# Arduino_4_Layers_TEST.net
KiCad netlist of a schematic drawn in EAGLE
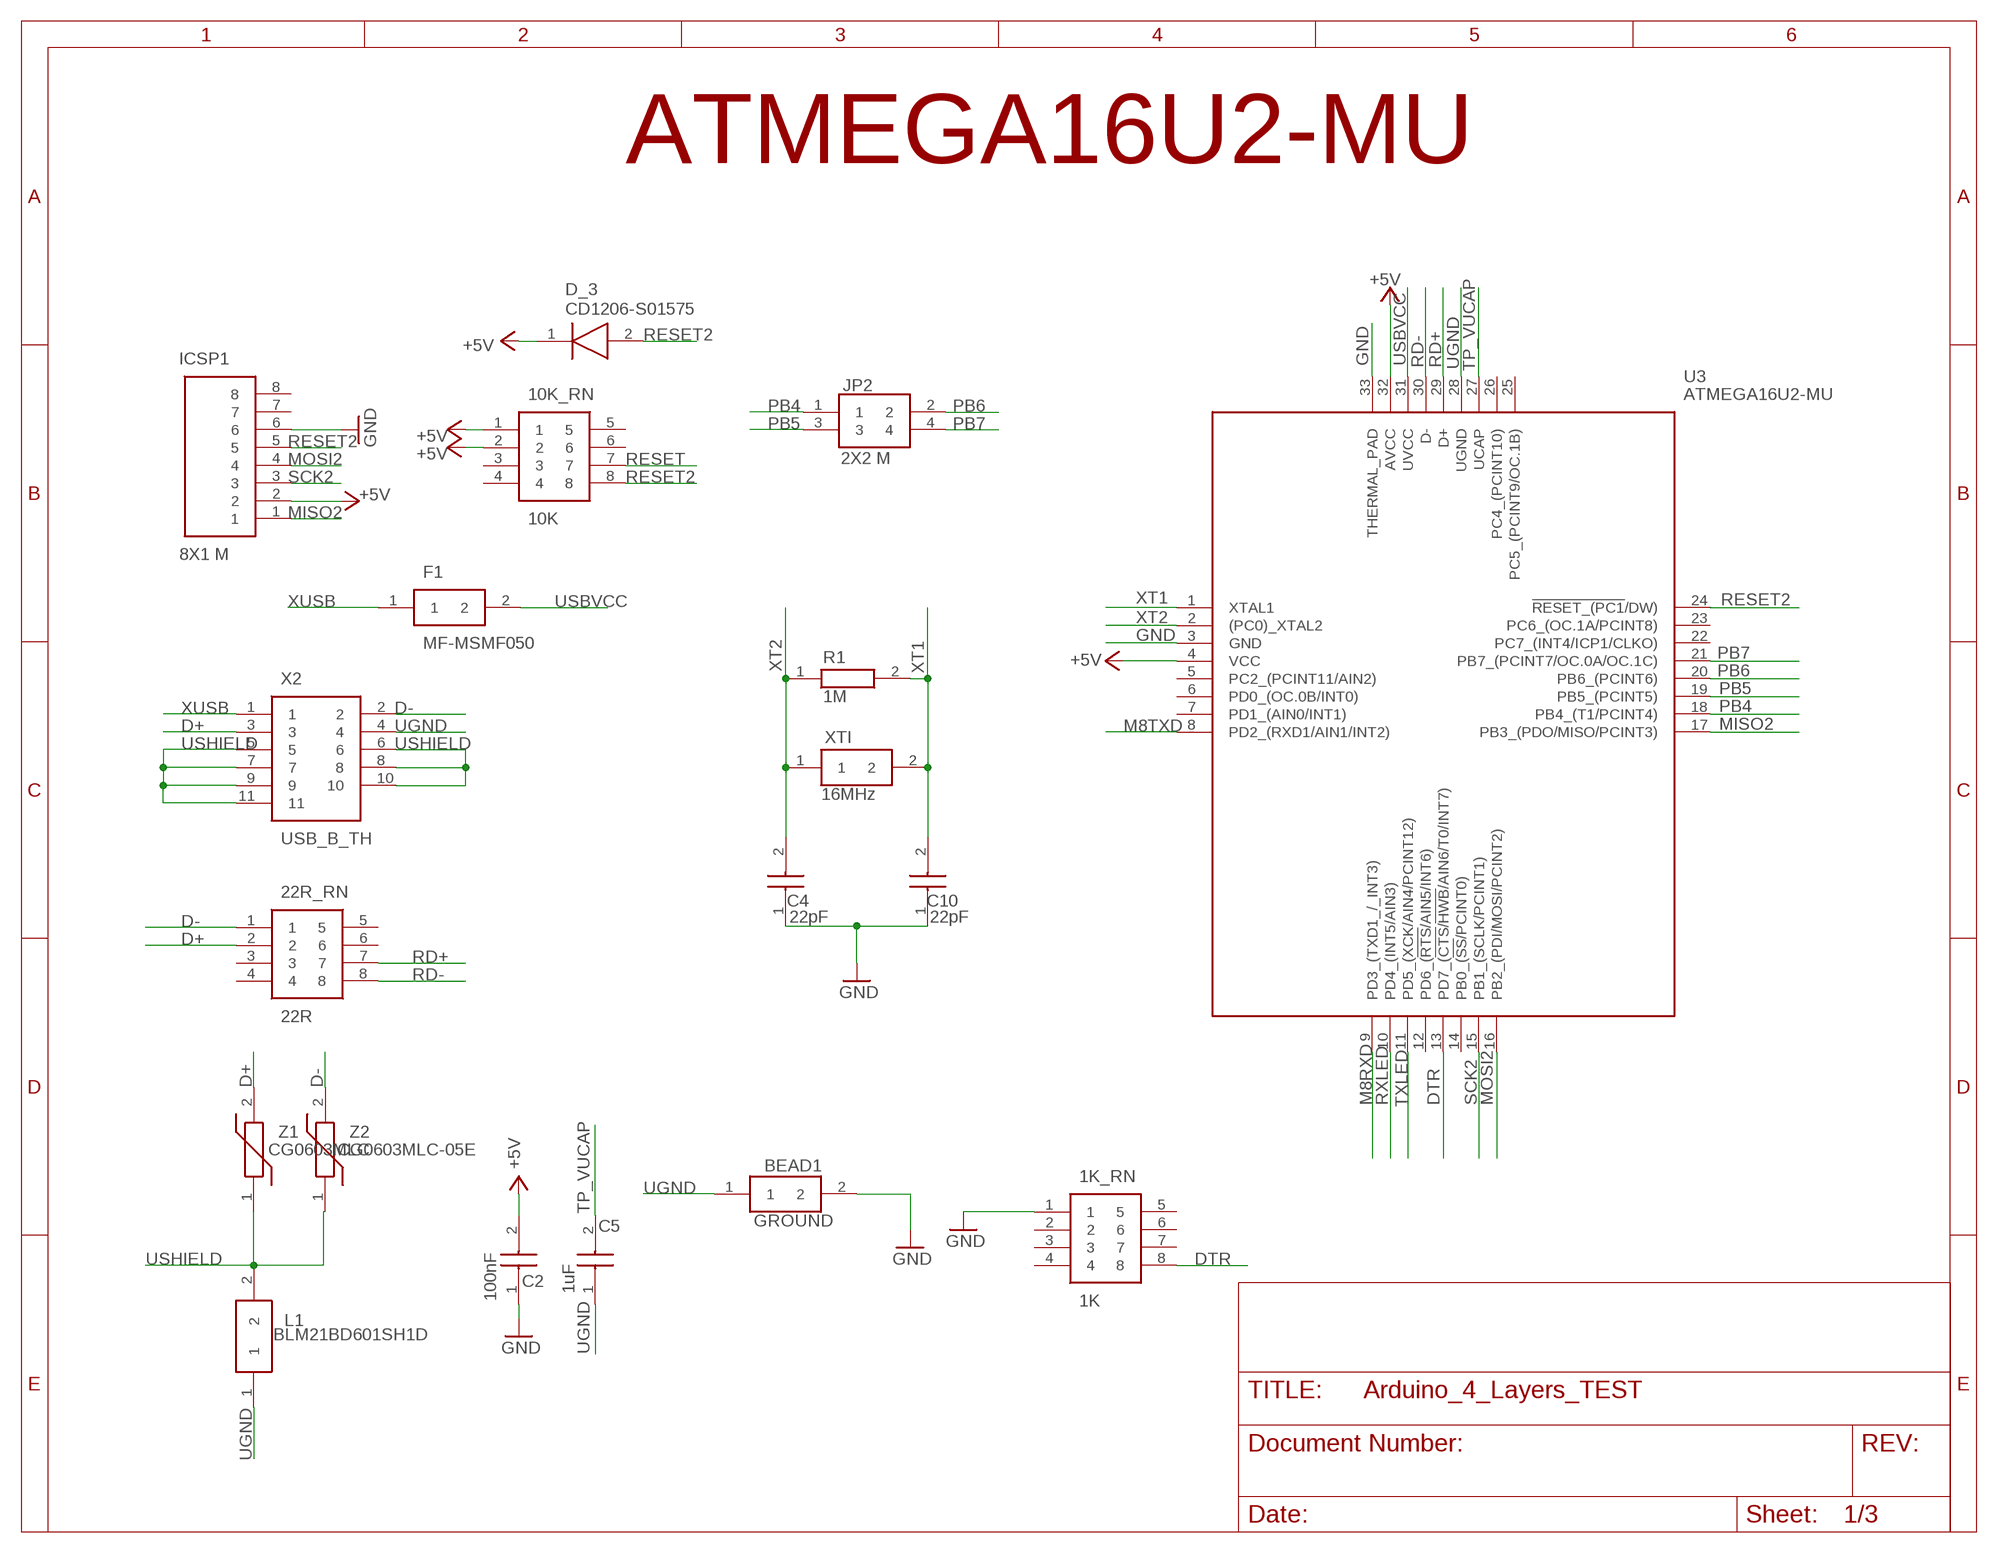
[diagram p0: schematic, sheet 1]
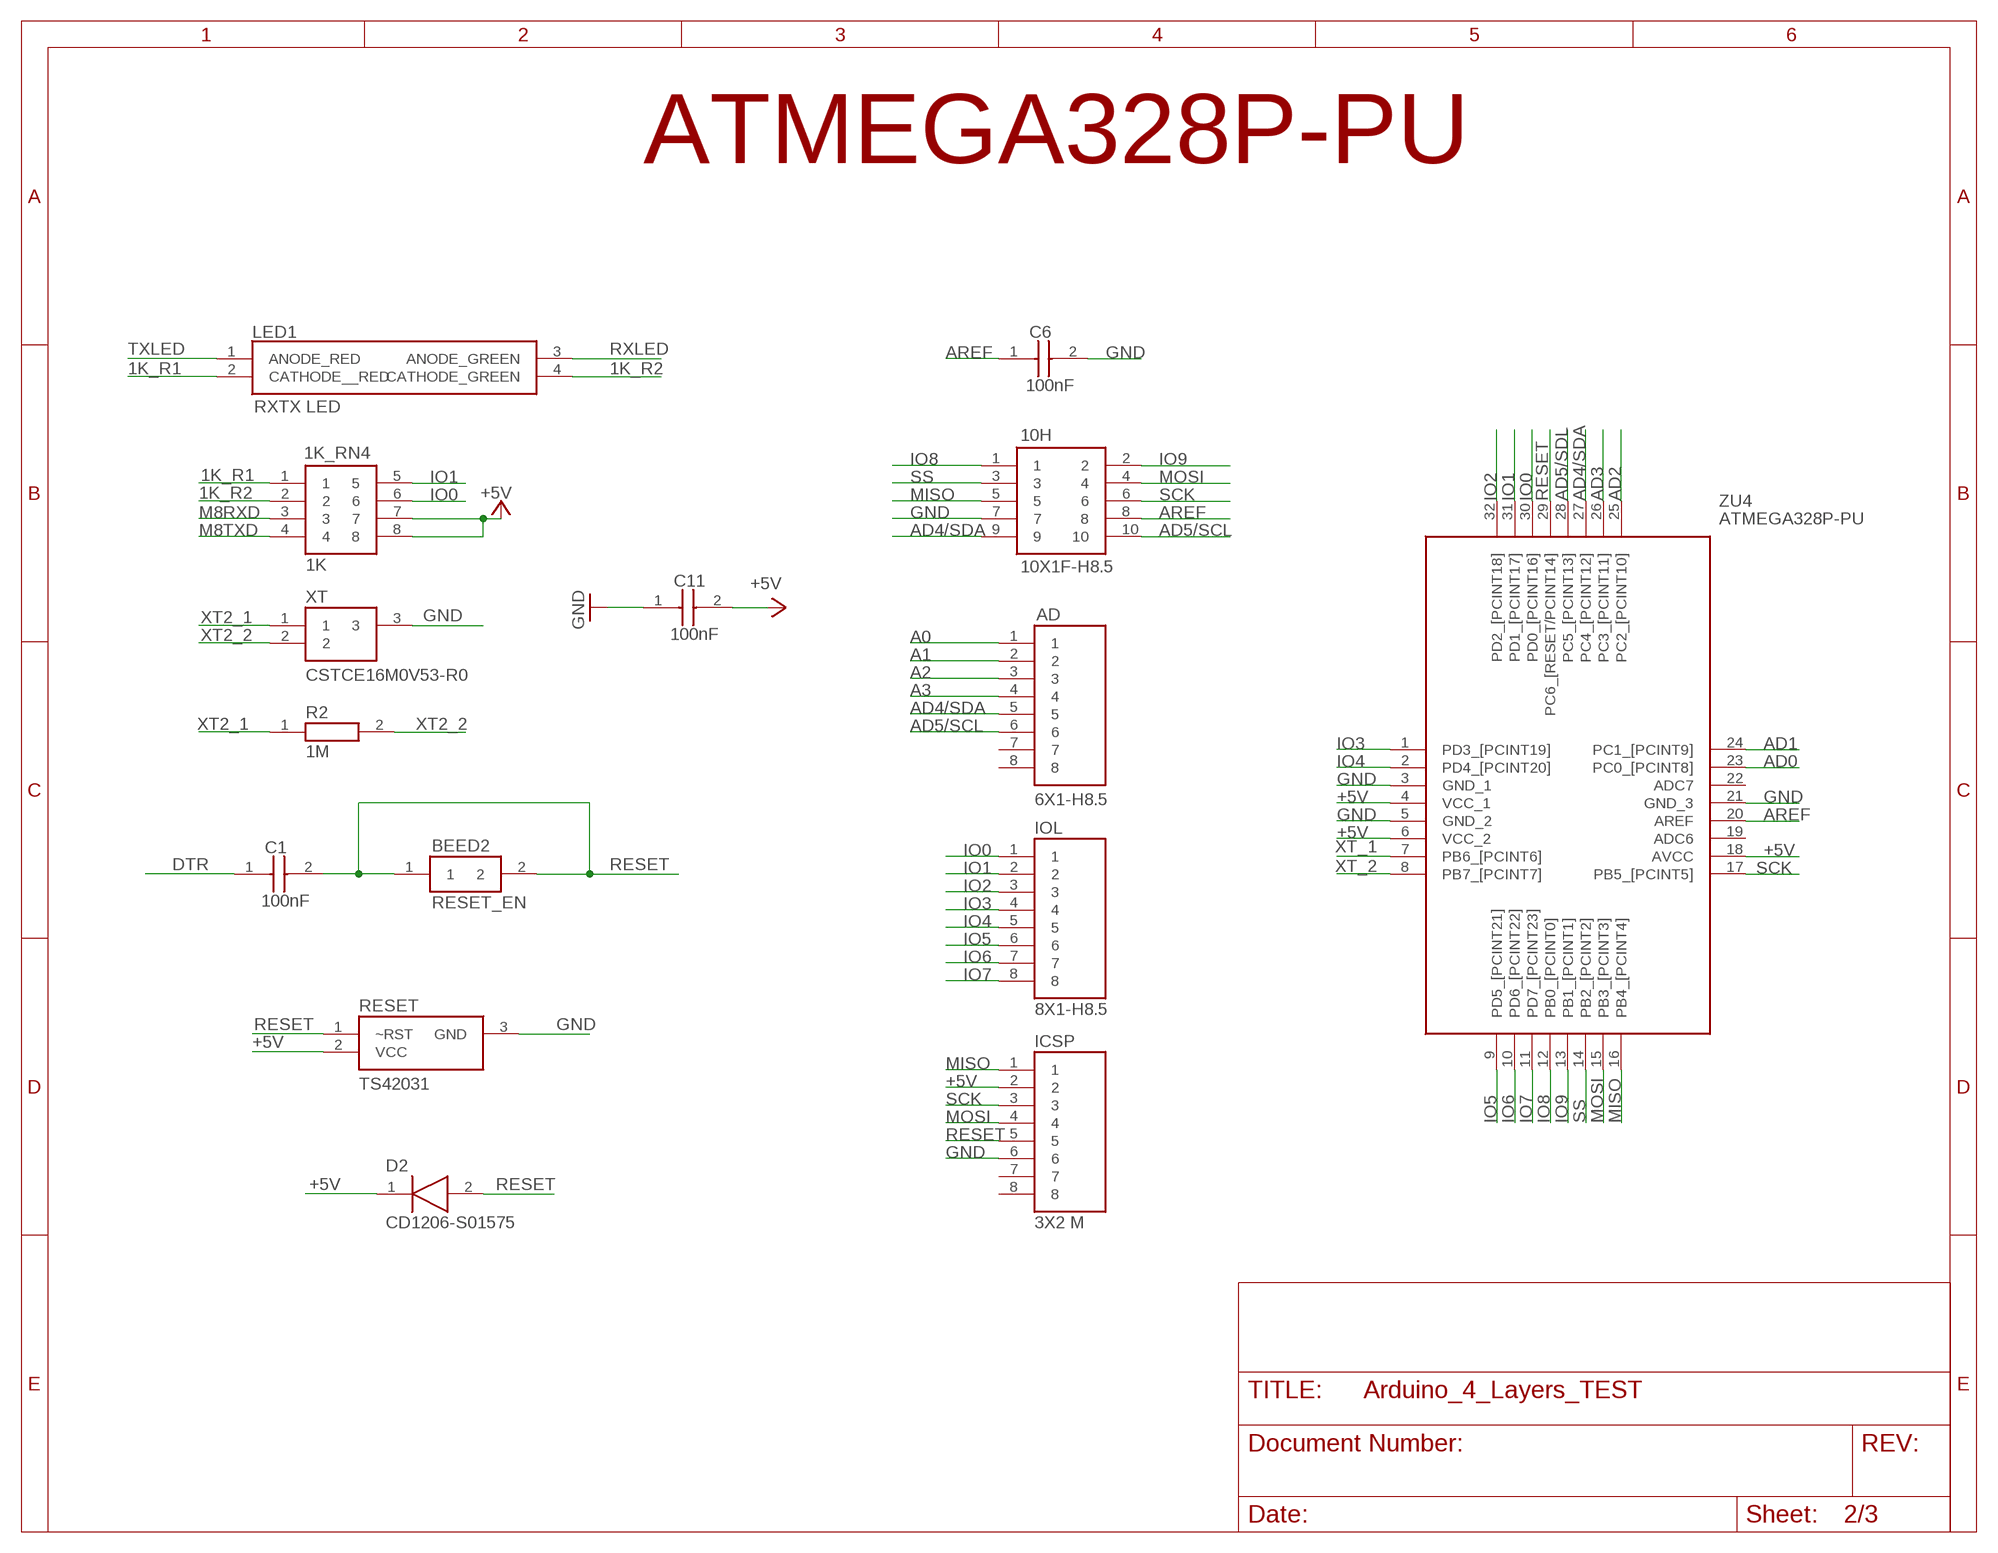
[diagram p1: schematic, sheet 2]
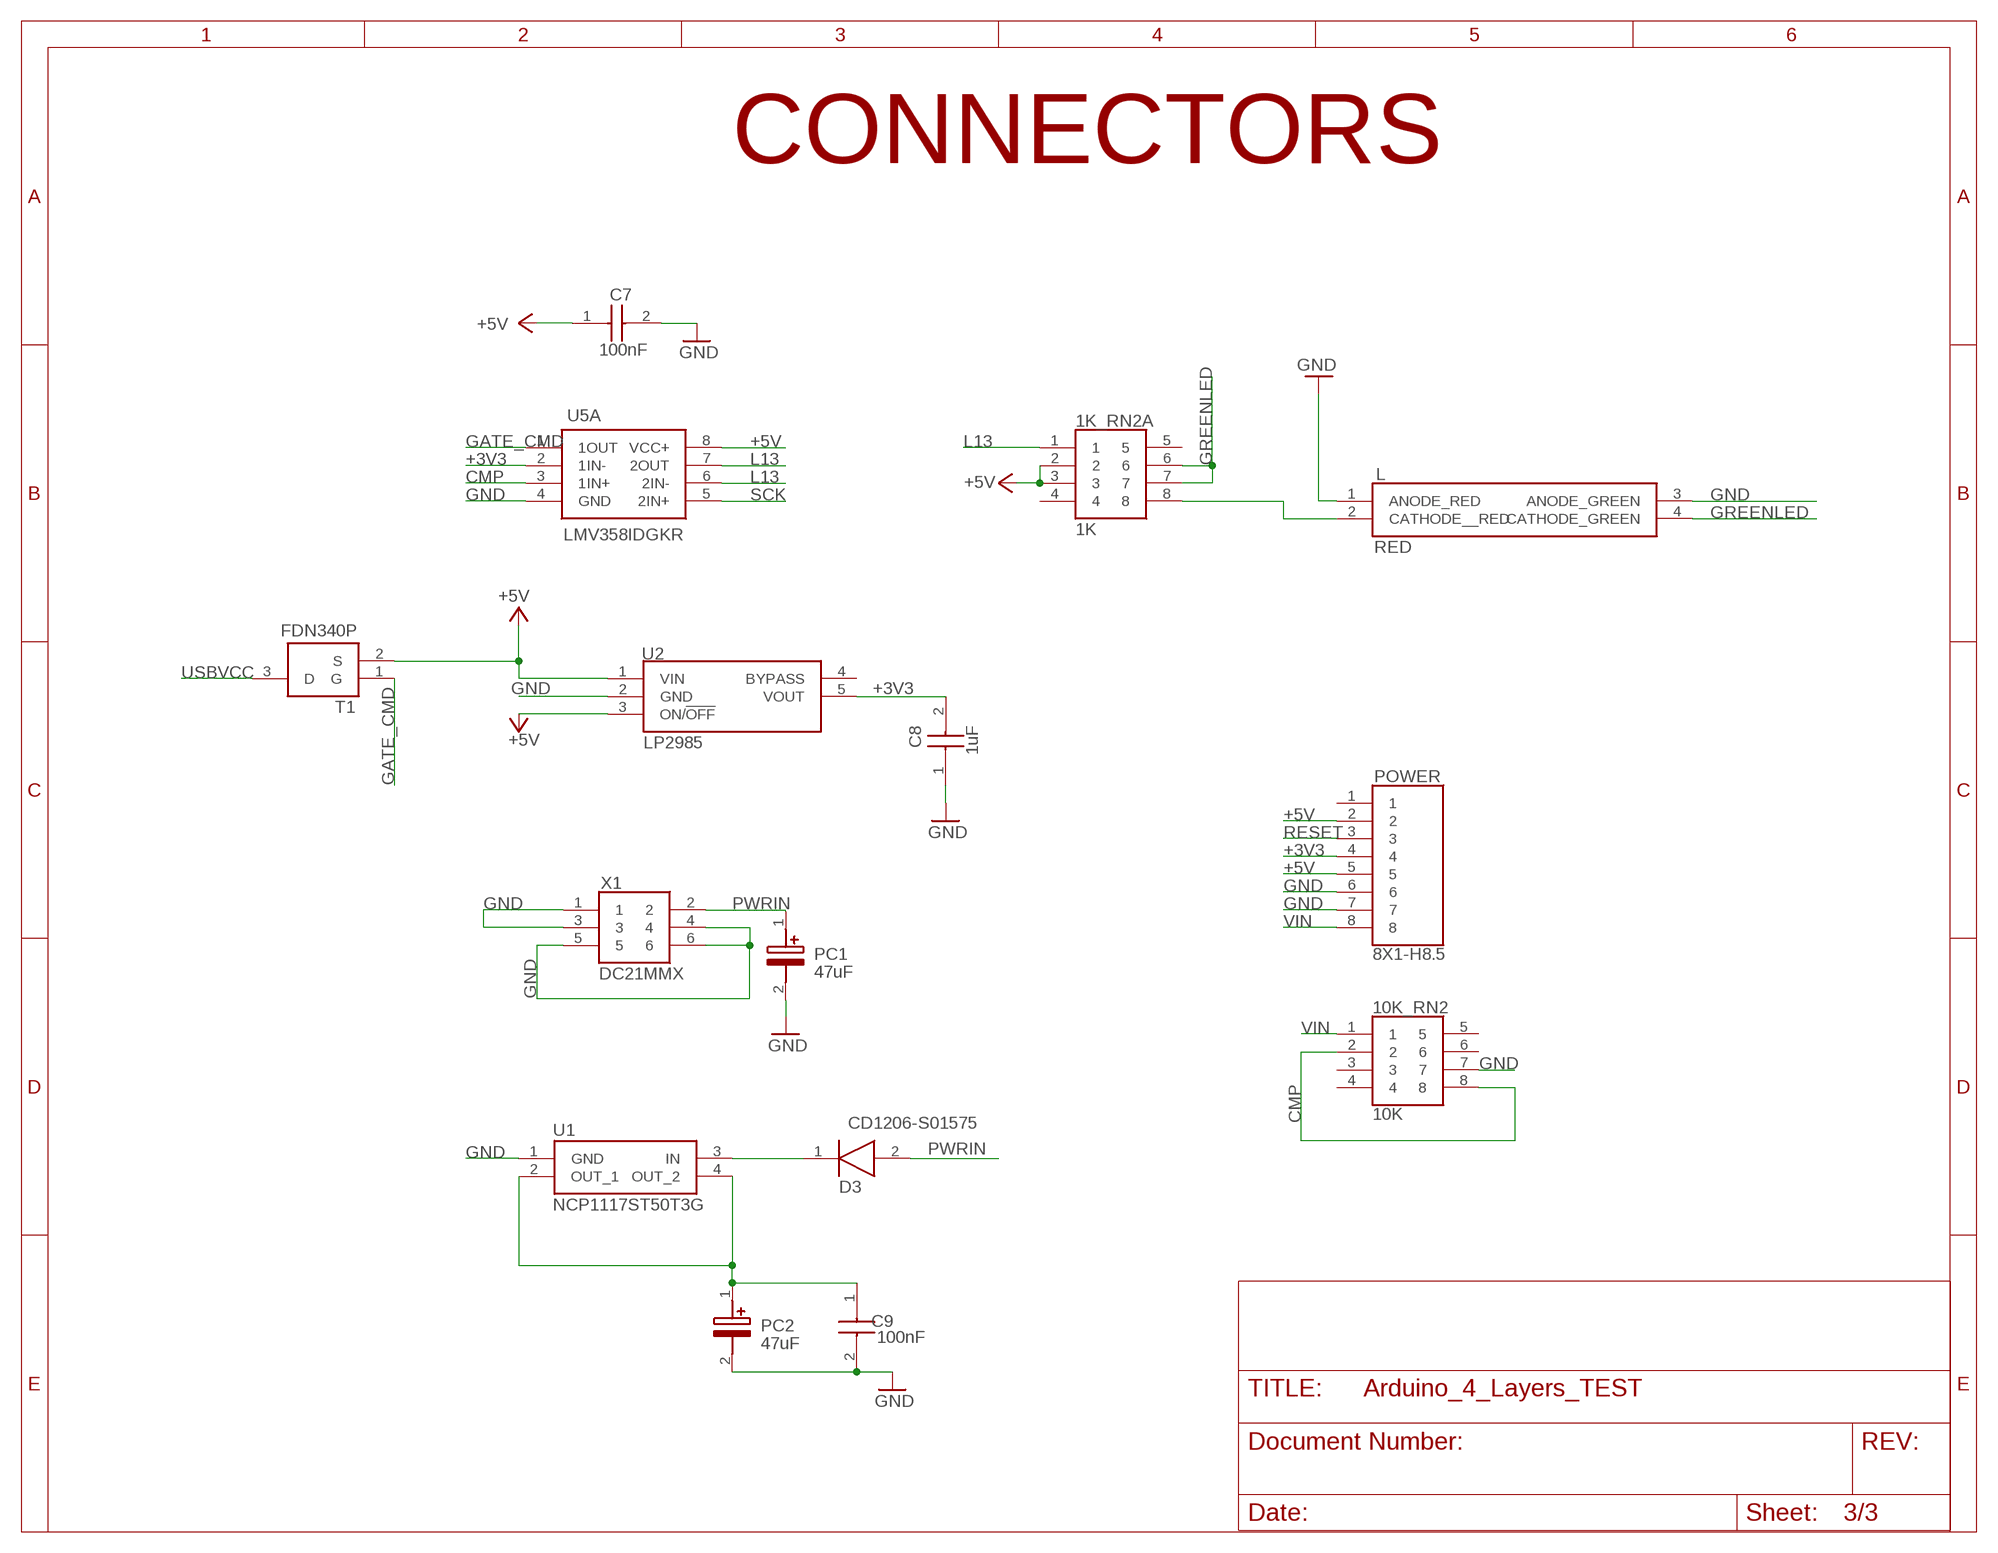
[diagram p2: schematic, sheet 3]

(export (version "E")
  (design (tool "Eeschema 10.0.6"))
  (components
    (comp (ref "1K_RN")
      (value "1K")
      (footprint "eagle-import:CAY10-XXXJ4")
      (fields
        (field (name "MANUFACTURER_PART_NUMBER") "CAY10-220J4LF")
        (field (name "MOUSER_PART_NUMBER") "652-CAY10-220J4LF")
        (field (name "RS_PART_NUMBER") "1674746")
      )
      (libsource (lib "eagle-import") (part "CAY10-220J4LF"))
    )
    (comp (ref "10K_RN")
      (value "10K")
      (footprint "eagle-import:CAY10-XXXJ4")
      (fields
        (field (name "MANUFACTURER_PART_NUMBER") "CAY10-220J4LF")
        (field (name "MOUSER_PART_NUMBER") "652-CAY10-220J4LF")
        (field (name "RS_PART_NUMBER") "1674746")
      )
      (libsource (lib "eagle-import") (part "CAY10-220J4LF"))
    )
    (comp (ref "22R_RN")
      (value "22R")
      (footprint "eagle-import:CAY10-XXXJ4")
      (fields
        (field (name "MANUFACTURER_PART_NUMBER") "CAY10-220J4LF")
        (field (name "MOUSER_PART_NUMBER") "652-CAY10-220J4LF")
        (field (name "RS_PART_NUMBER") "1674746")
      )
      (libsource (lib "eagle-import") (part "CAY10-220J4LF"))
    )
    (comp (ref "BEAD1")
      (value "GROUND")
      (footprint "eagle-import:BEADC2012X105N")
      (fields
        (field (name "MANUFACTURER_PART_NUMBER") "BLM21BD601SH1D")
        (field (name "MOUSER_PART_NUMBER") "81-BLM21BD601SH1D")
        (field (name "RS_PART_NUMBER") "1048541P")
      )
      (libsource (lib "eagle-import") (part "BLM21BD601SH1D"))
    )
    (comp (ref "C2")
      (value "100nF")
      (footprint "eagle-import:CAPC2012X130N")
      (fields
        (field (name "MANUFACTURER_PART_NUMBER") "0805Y0500104KXT")
        (field (name "MOUSER_PART_NUMBER") "7738389P")
      )
      (libsource (lib "eagle-import") (part "0805Y0500104KXT"))
    )
    (comp (ref "C4")
      (value "22pF")
      (footprint "eagle-import:CAPC2012X70N")
      (fields
        (field (name "MANUFACTURER_PART_NUMBER") "GRM2165C1H220JZ01D")
        (field (name "MOUSER_PART_NUMBER") "81-GRM2165C1H220JZ")
        (field (name "RS_PART_NUMBER") "7236243")
      )
      (libsource (lib "eagle-import") (part "GRM2165C1H220JZ01D"))
    )
    (comp (ref "C5")
      (value "1uF")
      (footprint "eagle-import:CAPC2012X145N")
      (fields
        (field (name "MANUFACTURER_PART_NUMBER") "C2012C0G2A103J125AA")
        (field (name "MOUSER_PART_NUMBER") "810-C2012C0G2A103JAA")
      )
      (libsource (lib "eagle-import") (part "C2012C0G2A103J125AA"))
    )
    (comp (ref "C10")
      (value "22pF")
      (footprint "eagle-import:CAPC2012X70N")
      (fields
        (field (name "MANUFACTURER_PART_NUMBER") "GRM2165C1H220JZ01D")
        (field (name "MOUSER_PART_NUMBER") "81-GRM2165C1H220JZ")
        (field (name "RS_PART_NUMBER") "7236243")
      )
      (libsource (lib "eagle-import") (part "GRM2165C1H220JZ01D"))
    )
    (comp (ref "D_3")
      (value "CD1206-S01575")
      (footprint "eagle-import:DIOC3016X65N")
      (fields
        (field (name "MOUSER_PART_NUMBER") "652-CD1206-S01575")
        (field (name "RS_PART_NUMBER") "1775431")
      )
      (libsource (lib "eagle-import") (part "CD1206-S01575"))
    )
    (comp (ref "F1")
      (value "MF-MSMF050")
      (footprint "eagle-import:FUSC4632X75N")
      (fields
        (field (name "MANUFACTURER_PART_NUMBER") "1812L050/30PR")
        (field (name "MOUSER_PART_NUMBER") "576-1812L050/30PR")
        (field (name "RS_PART_NUMBER") "8951631P")
      )
      (libsource (lib "eagle-import") (part "1812L050_30PR"))
    )
    (comp (ref "ICSP1")
      (value "8X1 M")
      (footprint "eagle-import:HDRV8W90P0X254_1X8_2032X249X56")
      (fields
        (field (name "MANUFACTURER_PART_NUMBER") "90120-0768")
        (field (name "MOUSER_PART_NUMBER") "538-90120-0768")
        (field (name "RS_PART_NUMBER") "1671900")
      )
      (libsource (lib "eagle-import") (part "90120-0768"))
    )
    (comp (ref "JP2")
      (value "2X2 M")
      (footprint "eagle-import:HDRV4W77P254_2X2_467X488X821P")
      (fields
        (field (name "MANUFACTURER_PART_NUMBER") "5-146256-2")
        (field (name "MOUSER_PART_NUMBER") "571-5-146256-2")
        (field (name "RS_PART_NUMBER") "7972955")
      )
      (libsource (lib "eagle-import") (part "5-146256-2"))
    )
    (comp (ref "L1")
      (value "BLM21BD601SH1D")
      (footprint "eagle-import:BEADC2012X105N")
      (fields
        (field (name "MOUSER_PART_NUMBER") "81-BLM21BD601SH1D")
        (field (name "RS_PART_NUMBER") "1048541P")
      )
      (libsource (lib "eagle-import") (part "BLM21BD601SH1D"))
    )
    (comp (ref "R1")
      (value "1M")
      (footprint "eagle-import:RESC1608X55N")
      (fields
        (field (name "MANUFACTURER_PART_NUMBER") "CPF0603B1M0E1")
        (field (name "MOUSER_PART_NUMBER") "279-CPF0603B1M0E1")
      )
      (libsource (lib "eagle-import") (part "CPF0603B1M0E1"))
    )
    (comp (ref "U3")
      (value "ATMEGA16U2-MU")
      (footprint "eagle-import:QFN50P500X500X100-33N")
      (fields
        (field (name "MOUSER_PART_NUMBER") "556-ATMEGA16U2-MU")
        (field (name "RS_PART_NUMBER") "1717746")
      )
      (libsource (lib "eagle-import") (part "ATMEGA16U2-MU"))
    )
    (comp (ref "X2")
      (value "USB_B_TH")
      (footprint "eagle-import:17340351")
      (fields
        (field (name "MANUFACTURER_PART_NUMBER") "1734035-1")
        (field (name "MOUSER_PART_NUMBER") "571-1734035-1")
      )
      (libsource (lib "eagle-import") (part "1734035-1"))
    )
    (comp (ref "XTI")
      (value "16MHz")
      (footprint "eagle-import:MODEL-445")
      (fields
        (field (name "MANUFACTURER_PART_NUMBER") "445I35D16M00000")
        (field (name "MOUSER_PART_NUMBER") "774-445I35D16M00000")
      )
      (libsource (lib "eagle-import") (part "445I35D16M00000"))
    )
    (comp (ref "Z1")
      (value "CG0603MLC")
      (footprint "eagle-import:VARC1608X55N")
      (fields
        (field (name "MANUFACTURER_PART_NUMBER") "CG0603MLC-05E")
        (field (name "MOUSER_PART_NUMBER") "652-CG0603MLC-05E")
        (field (name "RS_PART_NUMBER") "8518256")
      )
      (libsource (lib "eagle-import") (part "CG0603MLC-05E"))
    )
    (comp (ref "Z2")
      (value "CG0603MLC-05E")
      (footprint "eagle-import:VARC1608X55N")
      (fields
        (field (name "MOUSER_PART_NUMBER") "652-CG0603MLC-05E")
        (field (name "RS_PART_NUMBER") "8518256")
      )
      (libsource (lib "eagle-import") (part "CG0603MLC-05E"))
    )
    (comp (ref "1K_RN4")
      (value "1K")
      (footprint "eagle-import:CAY10-XXXJ4")
      (fields
        (field (name "MANUFACTURER_PART_NUMBER") "CAY10-220J4LF")
        (field (name "MOUSER_PART_NUMBER") "652-CAY10-220J4LF")
        (field (name "RS_PART_NUMBER") "1674746")
      )
      (libsource (lib "eagle-import") (part "CAY10-220J4LF"))
    )
    (comp (ref "10H")
      (value "10X1F-H8.5")
      (footprint "eagle-import:FTMH10503LDV")
      (fields
        (field (name "MANUFACTURER_PART_NUMBER") "FTMH-105-03-L-DV")
        (field (name "MOUSER_PART_NUMBER") "200-FTMH10503LDV")
        (field (name "RS_PART_NUMBER") "7668984P")
      )
      (libsource (lib "eagle-import") (part "FTMH-105-03-L-DV"))
    )
    (comp (ref "AD")
      (value "6X1-H8.5")
      (footprint "eagle-import:HDRV8W90P0X254_1X8_2032X249X56")
      (fields
        (field (name "MANUFACTURER_PART_NUMBER") "90120-0768")
        (field (name "MOUSER_PART_NUMBER") "538-90120-0768")
        (field (name "RS_PART_NUMBER") "1671900")
      )
      (libsource (lib "eagle-import") (part "90120-0768"))
    )
    (comp (ref "BEED2")
      (value "RESET_EN")
      (footprint "eagle-import:BEADC2012X105N")
      (fields
        (field (name "MANUFACTURER_PART_NUMBER") "BLM21BD601SH1D")
        (field (name "MOUSER_PART_NUMBER") "81-BLM21BD601SH1D")
        (field (name "RS_PART_NUMBER") "1048541P")
      )
      (libsource (lib "eagle-import") (part "BLM21BD601SH1D"))
    )
    (comp (ref "C1")
      (value "100nF")
      (footprint "eagle-import:CAPC2012X130N")
      (fields
        (field (name "MANUFACTURER_PART_NUMBER") "0805Y0500104KXT")
        (field (name "MOUSER_PART_NUMBER") "7738389P")
      )
      (libsource (lib "eagle-import") (part "0805Y0500104KXT"))
    )
    (comp (ref "C6")
      (value "100nF")
      (footprint "eagle-import:CAPC2012X130N")
      (fields
        (field (name "MANUFACTURER_PART_NUMBER") "0805Y0500104KXT")
        (field (name "MOUSER_PART_NUMBER") "7738389P")
      )
      (libsource (lib "eagle-import") (part "0805Y0500104KXT"))
    )
    (comp (ref "C11")
      (value "100nF")
      (footprint "eagle-import:CAPC2012X130N")
      (fields
        (field (name "MANUFACTURER_PART_NUMBER") "0805Y0500104KXT")
        (field (name "MOUSER_PART_NUMBER") "7738389P")
      )
      (libsource (lib "eagle-import") (part "0805Y0500104KXT"))
    )
    (comp (ref "D2")
      (value "CD1206-S01575")
      (footprint "eagle-import:DIOC3016X65N")
      (fields
        (field (name "MOUSER_PART_NUMBER") "652-CD1206-S01575")
        (field (name "RS_PART_NUMBER") "1775431")
      )
      (libsource (lib "eagle-import") (part "CD1206-S01575"))
    )
    (comp (ref "ICSP")
      (value "3X2 M")
      (footprint "eagle-import:HDRV8W90P0X254_1X8_2032X249X56")
      (fields
        (field (name "MANUFACTURER_PART_NUMBER") "90120-0768")
        (field (name "MOUSER_PART_NUMBER") "538-90120-0768")
        (field (name "RS_PART_NUMBER") "1671900")
      )
      (libsource (lib "eagle-import") (part "90120-0768"))
    )
    (comp (ref "IOL")
      (value "8X1-H8.5")
      (footprint "eagle-import:HDRV8W90P0X254_1X8_2032X249X56")
      (fields
        (field (name "MANUFACTURER_PART_NUMBER") "90120-0768")
        (field (name "MOUSER_PART_NUMBER") "538-90120-0768")
        (field (name "RS_PART_NUMBER") "1671900")
      )
      (libsource (lib "eagle-import") (part "90120-0768"))
    )
    (comp (ref "LED1")
      (value "RXTX LED")
      (footprint "eagle-import:SML522MD8WT86")
      (fields
        (field (name "MANUFACTURER_PART_NUMBER") "SML-522MU8WT86")
        (field (name "MOUSER_PART_NUMBER") "755-SML-522MU8WT86")
        (field (name "RS_PART_NUMBER") "1682468")
      )
      (libsource (lib "eagle-import") (part "SML-522MU8WT86"))
    )
    (comp (ref "R2")
      (value "1M")
      (footprint "eagle-import:RESC1608X55N")
      (fields
        (field (name "MANUFACTURER_PART_NUMBER") "CPF0603B1M0E1")
        (field (name "MOUSER_PART_NUMBER") "279-CPF0603B1M0E1")
      )
      (libsource (lib "eagle-import") (part "CPF0603B1M0E1"))
    )
    (comp (ref "RESET")
      (value "TS42031")
      (footprint "eagle-import:SOT95P240X110-3N")
      (fields (field (name "MANUFACTURER_PART_NUMBER") "DS1818R-5+"))
      (libsource (lib "eagle-import") (part "DS1818R-5+"))
    )
    (comp (ref "XT")
      (value "CSTCE16M0V53-R0")
      (footprint "eagle-import:CSTCE-V")
      (fields
        (field (name "MOUSER_PART_NUMBER") "81-CSTCE16M0V53-R0")
        (field (name "RS_PART_NUMBER") "7926524P")
      )
      (libsource (lib "eagle-import") (part "CSTCE16M0V53-R0"))
    )
    (comp (ref "ZU4")
      (value "ATMEGA328P-PU")
      (footprint "eagle-import:QFP80P900X900X120-32N")
      (fields
        (field (name "MANUFACTURER_PART_NUMBER") "ATMEGA328P-AU")
        (field (name "MOUSER_PART_NUMBER") "556-ATMEGA328P-AU")
        (field (name "RS_PART_NUMBER") "1310271")
      )
      (libsource (lib "eagle-import") (part "ATMEGA328P-AU"))
    )
    (comp (ref "1K_RN2A")
      (value "1K")
      (footprint "eagle-import:CAY10-XXXJ4")
      (fields
        (field (name "MANUFACTURER_PART_NUMBER") "CAY10-220J4LF")
        (field (name "MOUSER_PART_NUMBER") "652-CAY10-220J4LF")
        (field (name "RS_PART_NUMBER") "1674746")
      )
      (libsource (lib "eagle-import") (part "CAY10-220J4LF"))
    )
    (comp (ref "10K_RN2")
      (value "10K")
      (footprint "eagle-import:CAY10-XXXJ4")
      (fields
        (field (name "MANUFACTURER_PART_NUMBER") "CAY10-220J4LF")
        (field (name "MOUSER_PART_NUMBER") "652-CAY10-220J4LF")
        (field (name "RS_PART_NUMBER") "1674746")
      )
      (libsource (lib "eagle-import") (part "CAY10-220J4LF"))
    )
    (comp (ref "C7")
      (value "100nF")
      (footprint "eagle-import:CAPC2012X130N")
      (fields
        (field (name "MANUFACTURER_PART_NUMBER") "0805Y0500104KXT")
        (field (name "MOUSER_PART_NUMBER") "7738389P")
      )
      (libsource (lib "eagle-import") (part "0805Y0500104KXT"))
    )
    (comp (ref "C8")
      (value "1uF")
      (footprint "eagle-import:CAPC2012X145N")
      (fields
        (field (name "MANUFACTURER_PART_NUMBER") "C2012C0G2A103J125AA")
        (field (name "MOUSER_PART_NUMBER") "810-C2012C0G2A103JAA")
      )
      (libsource (lib "eagle-import") (part "C2012C0G2A103J125AA"))
    )
    (comp (ref "C9")
      (value "100nF")
      (footprint "eagle-import:CAPC2012X130N")
      (fields
        (field (name "MANUFACTURER_PART_NUMBER") "0805Y0500104KXT")
        (field (name "MOUSER_PART_NUMBER") "7738389P")
      )
      (libsource (lib "eagle-import") (part "0805Y0500104KXT"))
    )
    (comp (ref "D3")
      (value "CD1206-S01575")
      (footprint "eagle-import:DIOC3016X65N")
      (fields
        (field (name "MOUSER_PART_NUMBER") "652-CD1206-S01575")
        (field (name "RS_PART_NUMBER") "1775431")
      )
      (libsource (lib "eagle-import") (part "CD1206-S01575"))
    )
    (comp (ref "L")
      (value "RED")
      (footprint "eagle-import:SML522MD8WT86")
      (fields
        (field (name "MANUFACTURER_PART_NUMBER") "SML-522MU8WT86")
        (field (name "MOUSER_PART_NUMBER") "755-SML-522MU8WT86")
        (field (name "RS_PART_NUMBER") "1682468")
      )
      (libsource (lib "eagle-import") (part "SML-522MU8WT86"))
    )
    (comp (ref "PC1")
      (value "47uF")
      (footprint "eagle-import:CAPAE530X610N")
      (fields
        (field (name "MANUFACTURER_PART_NUMBER") "EEE-FT1V470AR")
        (field (name "MOUSER_PART_NUMBER") "667-EEE-FT1V470AR")
      )
      (libsource (lib "eagle-import") (part "EEE-FT1V470AR"))
    )
    (comp (ref "PC2")
      (value "47uF")
      (footprint "eagle-import:CAPAE530X610N")
      (fields
        (field (name "MANUFACTURER_PART_NUMBER") "EEE-FT1V470AR")
        (field (name "MOUSER_PART_NUMBER") "667-EEE-FT1V470AR")
      )
      (libsource (lib "eagle-import") (part "EEE-FT1V470AR"))
    )
    (comp (ref "POWER")
      (value "8X1-H8.5")
      (footprint "eagle-import:HDRV8W90P0X254_1X8_2032X249X56")
      (fields
        (field (name "MANUFACTURER_PART_NUMBER") "90120-0768")
        (field (name "MOUSER_PART_NUMBER") "538-90120-0768")
        (field (name "RS_PART_NUMBER") "1671900")
      )
      (libsource (lib "eagle-import") (part "90120-0768"))
    )
    (comp (ref "T1")
      (value "FDN340P")
      (footprint "eagle-import:SOT95P251X112-3N")
      (fields (field (name "MOUSER_PART_NUMBER") "512-FDN340P") (field (name "RS_PART_NUMBER") "6710435P"))
      (libsource (lib "eagle-import") (part "FDN340P"))
    )
    (comp (ref "U1")
      (value "NCP1117ST50T3G")
      (footprint "eagle-import:SOT230P700X180-4N")
      (fields
        (field (name "MOUSER_PART_NUMBER") "863-NCP1117ST50T3G")
        (field (name "RS_PART_NUMBER") "8022130P")
      )
      (libsource (lib "eagle-import") (part "NCP1117ST50T3G"))
    )
    (comp (ref "U2")
      (value "LP2985")
      (footprint "eagle-import:SOT95P280X145-5N")
      (fields
        (field (name "MANUFACTURER_PART_NUMBER") "LP2985-33DBVR")
        (field (name "MOUSER_PART_NUMBER") "595-LP2985-33DBVR")
      )
      (libsource (lib "eagle-import") (part "LP2985-33DBVR"))
    )
    (comp (ref "U5A")
      (value "LMV358IDGKR")
      (footprint "eagle-import:SOP65P490X110-8N")
      (fields (field (name "MOUSER_PART_NUMBER") "595-LMV358IDGKR") (field (name "RS_PART_NUMBER") "1625114"))
      (libsource (lib "eagle-import") (part "LMV358IDGKR"))
    )
    (comp (ref "X1")
      (value "DC21MMX")
      (footprint "eagle-import:USBBSRA")
      (fields (field (name "MANUFACTURER_PART_NUMBER") "USB-B-S-RA"))
      (libsource (lib "eagle-import") (part "USB-B-S-RA"))
    )
  )
  (nets
    (net (code "1") (name "+3V3") (class "Default")
      (node (ref "C8") (pin "2") (pinfunction "2_2") (pintype "bidirectional"))
      (node (ref "POWER") (pin "4") (pinfunction "4_4") (pintype "bidirectional"))
      (node (ref "U2") (pin "5") (pinfunction "VOUT_5") (pintype "output"))
      (node (ref "U5A") (pin "2") (pinfunction "1IN-_2") (pintype "input"))
    )
    (net (code "2") (name "+5V") (class "Default")
      (node (ref "10K_RN") (pin "1") (pinfunction "1_1") (pintype "bidirectional"))
      (node (ref "10K_RN") (pin "2") (pinfunction "2_2") (pintype "bidirectional"))
      (node (ref "1K_RN2A") (pin "2") (pinfunction "2_2") (pintype "bidirectional"))
      (node (ref "1K_RN2A") (pin "3") (pinfunction "3_3") (pintype "bidirectional"))
      (node (ref "1K_RN4") (pin "7") (pinfunction "7_7") (pintype "bidirectional"))
      (node (ref "1K_RN4") (pin "8") (pinfunction "8_8") (pintype "bidirectional"))
      (node (ref "C11") (pin "2") (pinfunction "2_2") (pintype "bidirectional"))
      (node (ref "C2") (pin "2") (pinfunction "2_2") (pintype "bidirectional"))
      (node (ref "C7") (pin "1") (pinfunction "1_1") (pintype "bidirectional"))
      (node (ref "D2") (pin "1") (pinfunction "K_1") (pintype "bidirectional"))
      (node (ref "D_3") (pin "1") (pinfunction "K_1") (pintype "bidirectional"))
      (node (ref "ICSP") (pin "2") (pinfunction "2_2") (pintype "bidirectional"))
      (node (ref "ICSP1") (pin "2") (pinfunction "2_2") (pintype "bidirectional"))
      (node (ref "POWER") (pin "2") (pinfunction "2_2") (pintype "bidirectional"))
      (node (ref "POWER") (pin "5") (pinfunction "5_5") (pintype "bidirectional"))
      (node (ref "RESET") (pin "2") (pinfunction "VCC_2") (pintype "bidirectional"))
      (node (ref "T1") (pin "2") (pinfunction "S_2") (pintype "bidirectional"))
      (node (ref "U2") (pin "1") (pinfunction "VIN_1") (pintype "power_in"))
      (node (ref "U2") (pin "3") (pinfunction "ON/~{OFF}_3") (pintype "input"))
      (node (ref "U3") (pin "32") (pinfunction "AVCC_32") (pintype "bidirectional"))
      (node (ref "U3") (pin "4") (pinfunction "VCC_4") (pintype "bidirectional"))
      (node (ref "U5A") (pin "8") (pinfunction "VCC+_8") (pintype "power_in"))
      (node (ref "ZU4") (pin "18") (pinfunction "AVCC_18") (pintype "power_in"))
      (node (ref "ZU4") (pin "4") (pinfunction "VCC_1_4") (pintype "power_in"))
      (node (ref "ZU4") (pin "6") (pinfunction "VCC_2_6") (pintype "power_in"))
    )
    (net (code "3") (name "1K_R1") (class "Default")
      (node (ref "1K_RN4") (pin "1") (pinfunction "1_1") (pintype "bidirectional"))
      (node (ref "LED1") (pin "2") (pinfunction "CATHODE__RED_2") (pintype "bidirectional"))
    )
    (net (code "4") (name "1K_R2") (class "Default")
      (node (ref "1K_RN4") (pin "2") (pinfunction "2_2") (pintype "bidirectional"))
      (node (ref "LED1") (pin "4") (pinfunction "CATHODE_GREEN_4") (pintype "bidirectional"))
    )
    (net (code "5") (name "A0") (class "Default")
      (node (ref "AD") (pin "1") (pinfunction "1_1") (pintype "bidirectional"))
    )
    (net (code "6") (name "A1") (class "Default")
      (node (ref "AD") (pin "2") (pinfunction "2_2") (pintype "bidirectional"))
    )
    (net (code "7") (name "A2") (class "Default")
      (node (ref "AD") (pin "3") (pinfunction "3_3") (pintype "bidirectional"))
    )
    (net (code "8") (name "A3") (class "Default")
      (node (ref "AD") (pin "4") (pinfunction "4_4") (pintype "bidirectional"))
    )
    (net (code "9") (name "AD0") (class "Default")
      (node (ref "ZU4") (pin "23") (pinfunction "PC0_[PCINT8]_23") (pintype "bidirectional"))
    )
    (net (code "10") (name "AD1") (class "Default")
      (node (ref "ZU4") (pin "24") (pinfunction "PC1_[PCINT9]_24") (pintype "bidirectional"))
    )
    (net (code "11") (name "AD2") (class "Default")
      (node (ref "ZU4") (pin "25") (pinfunction "PC2_[PCINT10]_25") (pintype "bidirectional"))
    )
    (net (code "12") (name "AD3") (class "Default")
      (node (ref "ZU4") (pin "26") (pinfunction "PC3_[PCINT11]_26") (pintype "bidirectional"))
    )
    (net (code "13") (name "AD4{slash}SDA") (class "Default")
      (node (ref "10H") (pin "9") (pinfunction "9_9") (pintype "bidirectional"))
      (node (ref "AD") (pin "5") (pinfunction "5_5") (pintype "bidirectional"))
      (node (ref "ZU4") (pin "27") (pinfunction "PC4_[PCINT12]_27") (pintype "bidirectional"))
    )
    (net (code "14") (name "AD5{slash}SCL") (class "Default")
      (node (ref "10H") (pin "10") (pinfunction "10_10") (pintype "bidirectional"))
      (node (ref "AD") (pin "6") (pinfunction "6_6") (pintype "bidirectional"))
    )
    (net (code "15") (name "AD5{slash}SDL") (class "Default")
      (node (ref "ZU4") (pin "28") (pinfunction "PC5_[PCINT13]_28") (pintype "bidirectional"))
    )
    (net (code "16") (name "AREF") (class "Default")
      (node (ref "10H") (pin "8") (pinfunction "8_8") (pintype "bidirectional"))
      (node (ref "C6") (pin "1") (pinfunction "1_1") (pintype "bidirectional"))
      (node (ref "ZU4") (pin "20") (pinfunction "AREF_20") (pintype "bidirectional"))
    )
    (net (code "17") (name "CMP") (class "Default")
      (node (ref "10K_RN2") (pin "2") (pinfunction "2_2") (pintype "bidirectional"))
      (node (ref "10K_RN2") (pin "8") (pinfunction "8_8") (pintype "bidirectional"))
      (node (ref "U5A") (pin "3") (pinfunction "1IN+_3") (pintype "input"))
    )
    (net (code "18") (name "D+") (class "Default")
      (node (ref "22R_RN") (pin "2") (pinfunction "2_2") (pintype "bidirectional"))
      (node (ref "X2") (pin "3") (pinfunction "3_3") (pintype "bidirectional"))
      (node (ref "Z1") (pin "2") (pinfunction "2_2") (pintype "bidirectional"))
    )
    (net (code "19") (name "D-") (class "Default")
      (node (ref "22R_RN") (pin "1") (pinfunction "1_1") (pintype "bidirectional"))
      (node (ref "X2") (pin "2") (pinfunction "2_2") (pintype "bidirectional"))
      (node (ref "Z2") (pin "2") (pinfunction "2_2") (pintype "bidirectional"))
    )
    (net (code "20") (name "DTR") (class "Default")
      (node (ref "1K_RN") (pin "8") (pinfunction "8_8") (pintype "bidirectional"))
      (node (ref "C1") (pin "1") (pinfunction "1_1") (pintype "bidirectional"))
      (node (ref "U3") (pin "13") (pinfunction "PD7_(~{CTS}/~{HWB}/AIN6/T0/INT7)_13") (pintype "bidirectional"))
    )
    (net (code "21") (name "GATE_CMD") (class "Default")
      (node (ref "T1") (pin "1") (pinfunction "G_1") (pintype "bidirectional"))
      (node (ref "U5A") (pin "1") (pinfunction "1OUT_1") (pintype "output"))
    )
    (net (code "22") (name "GND") (class "Default")
      (node (ref "10H") (pin "7") (pinfunction "7_7") (pintype "bidirectional"))
      (node (ref "10K_RN2") (pin "7") (pinfunction "7_7") (pintype "bidirectional"))
      (node (ref "1K_RN") (pin "1") (pinfunction "1_1") (pintype "bidirectional"))
      (node (ref "BEAD1") (pin "2") (pinfunction "2_2") (pintype "bidirectional"))
      (node (ref "C10") (pin "1") (pinfunction "1_1") (pintype "bidirectional"))
      (node (ref "C11") (pin "1") (pinfunction "1_1") (pintype "bidirectional"))
      (node (ref "C2") (pin "1") (pinfunction "1_1") (pintype "bidirectional"))
      (node (ref "C4") (pin "1") (pinfunction "1_1") (pintype "bidirectional"))
      (node (ref "C6") (pin "2") (pinfunction "2_2") (pintype "bidirectional"))
      (node (ref "C7") (pin "2") (pinfunction "2_2") (pintype "bidirectional"))
      (node (ref "C8") (pin "1") (pinfunction "1_1") (pintype "bidirectional"))
      (node (ref "C9") (pin "2") (pinfunction "2_2") (pintype "bidirectional"))
      (node (ref "ICSP") (pin "6") (pinfunction "6_6") (pintype "bidirectional"))
      (node (ref "ICSP1") (pin "6") (pinfunction "6_6") (pintype "bidirectional"))
      (node (ref "L") (pin "1") (pinfunction "ANODE_RED_1") (pintype "bidirectional"))
      (node (ref "L") (pin "3") (pinfunction "ANODE_GREEN_3") (pintype "bidirectional"))
      (node (ref "PC1") (pin "2") (pinfunction "-_2") (pintype "bidirectional"))
      (node (ref "PC2") (pin "2") (pinfunction "-_2") (pintype "bidirectional"))
      (node (ref "POWER") (pin "6") (pinfunction "6_6") (pintype "bidirectional"))
      (node (ref "POWER") (pin "7") (pinfunction "7_7") (pintype "bidirectional"))
      (node (ref "RESET") (pin "3") (pinfunction "GND_3") (pintype "bidirectional"))
      (node (ref "U1") (pin "1") (pinfunction "GND_1") (pintype "power_in"))
      (node (ref "U2") (pin "2") (pinfunction "GND_2") (pintype "power_in"))
      (node (ref "U3") (pin "3") (pinfunction "GND_3") (pintype "bidirectional"))
      (node (ref "U3") (pin "33") (pinfunction "THERMAL_PAD_33") (pintype "bidirectional"))
      (node (ref "U5A") (pin "4") (pinfunction "GND_4") (pintype "power_in"))
      (node (ref "X1") (pin "1") (pinfunction "1_1") (pintype "bidirectional"))
      (node (ref "X1") (pin "3") (pinfunction "3_3") (pintype "bidirectional"))
      (node (ref "X1") (pin "4") (pinfunction "4_4") (pintype "bidirectional"))
      (node (ref "X1") (pin "5") (pinfunction "5_5") (pintype "bidirectional"))
      (node (ref "X1") (pin "6") (pinfunction "6_6") (pintype "bidirectional"))
      (node (ref "XT") (pin "3") (pinfunction "3_3") (pintype "bidirectional"))
      (node (ref "ZU4") (pin "21") (pinfunction "GND_3_21") (pintype "power_in"))
      (node (ref "ZU4") (pin "3") (pinfunction "GND_1_3") (pintype "power_in"))
      (node (ref "ZU4") (pin "5") (pinfunction "GND_2_5") (pintype "power_in"))
    )
    (net (code "23") (name "GREENLED") (class "Default")
      (node (ref "1K_RN2A") (pin "6") (pinfunction "6_6") (pintype "bidirectional"))
      (node (ref "1K_RN2A") (pin "7") (pinfunction "7_7") (pintype "bidirectional"))
      (node (ref "L") (pin "4") (pinfunction "CATHODE_GREEN_4") (pintype "bidirectional"))
    )
    (net (code "24") (name "IO0") (class "Default")
      (node (ref "1K_RN4") (pin "6") (pinfunction "6_6") (pintype "bidirectional"))
      (node (ref "IOL") (pin "1") (pinfunction "1_1") (pintype "bidirectional"))
      (node (ref "ZU4") (pin "30") (pinfunction "PD0_[PCINT16]_30") (pintype "bidirectional"))
    )
    (net (code "25") (name "IO1") (class "Default")
      (node (ref "1K_RN4") (pin "5") (pinfunction "5_5") (pintype "bidirectional"))
      (node (ref "IOL") (pin "2") (pinfunction "2_2") (pintype "bidirectional"))
      (node (ref "ZU4") (pin "31") (pinfunction "PD1_[PCINT17]_31") (pintype "bidirectional"))
    )
    (net (code "26") (name "IO2") (class "Default")
      (node (ref "IOL") (pin "3") (pinfunction "3_3") (pintype "bidirectional"))
      (node (ref "ZU4") (pin "32") (pinfunction "PD2_[PCINT18]_32") (pintype "bidirectional"))
    )
    (net (code "27") (name "IO3") (class "Default")
      (node (ref "IOL") (pin "4") (pinfunction "4_4") (pintype "bidirectional"))
      (node (ref "ZU4") (pin "1") (pinfunction "PD3_[PCINT19]_1") (pintype "bidirectional"))
    )
    (net (code "28") (name "IO4") (class "Default")
      (node (ref "IOL") (pin "5") (pinfunction "5_5") (pintype "bidirectional"))
      (node (ref "ZU4") (pin "2") (pinfunction "PD4_[PCINT20]_2") (pintype "bidirectional"))
    )
    (net (code "29") (name "IO5") (class "Default")
      (node (ref "IOL") (pin "6") (pinfunction "6_6") (pintype "bidirectional"))
      (node (ref "ZU4") (pin "9") (pinfunction "PD5_[PCINT21]_9") (pintype "bidirectional"))
    )
    (net (code "30") (name "IO6") (class "Default")
      (node (ref "IOL") (pin "7") (pinfunction "7_7") (pintype "bidirectional"))
      (node (ref "ZU4") (pin "10") (pinfunction "PD6_[PCINT22]_10") (pintype "bidirectional"))
    )
    (net (code "31") (name "IO7") (class "Default")
      (node (ref "IOL") (pin "8") (pinfunction "8_8") (pintype "bidirectional"))
      (node (ref "ZU4") (pin "11") (pinfunction "PD7_[PCINT23]_11") (pintype "bidirectional"))
    )
    (net (code "32") (name "IO8") (class "Default")
      (node (ref "10H") (pin "1") (pinfunction "1_1") (pintype "bidirectional"))
      (node (ref "ZU4") (pin "12") (pinfunction "PB0_[PCINT0]_12") (pintype "bidirectional"))
    )
    (net (code "33") (name "IO9") (class "Default")
      (node (ref "10H") (pin "2") (pinfunction "2_2") (pintype "bidirectional"))
      (node (ref "ZU4") (pin "13") (pinfunction "PB1_[PCINT1]_13") (pintype "bidirectional"))
    )
    (net (code "34") (name "L13") (class "Default")
      (node (ref "1K_RN2A") (pin "1") (pinfunction "1_1") (pintype "bidirectional"))
      (node (ref "U5A") (pin "6") (pinfunction "2IN-_6") (pintype "input"))
      (node (ref "U5A") (pin "7") (pinfunction "2OUT_7") (pintype "output"))
    )
    (net (code "35") (name "M8RXD") (class "Default")
      (node (ref "1K_RN4") (pin "3") (pinfunction "3_3") (pintype "bidirectional"))
      (node (ref "U3") (pin "9") (pinfunction "PD3_(TXD1_/_INT3)_9") (pintype "bidirectional"))
    )
    (net (code "36") (name "M8TXD") (class "Default")
      (node (ref "1K_RN4") (pin "4") (pinfunction "4_4") (pintype "bidirectional"))
      (node (ref "U3") (pin "8") (pinfunction "PD2_(RXD1/AIN1/INT2)_8") (pintype "bidirectional"))
    )
    (net (code "37") (name "MISO") (class "Default")
      (node (ref "10H") (pin "5") (pinfunction "5_5") (pintype "bidirectional"))
      (node (ref "ICSP") (pin "1") (pinfunction "1_1") (pintype "bidirectional"))
      (node (ref "ZU4") (pin "16") (pinfunction "PB4_[PCINT4]_16") (pintype "bidirectional"))
    )
    (net (code "38") (name "MISO2") (class "Default")
      (node (ref "ICSP1") (pin "1") (pinfunction "1_1") (pintype "bidirectional"))
      (node (ref "U3") (pin "17") (pinfunction "PB3_(PDO/MISO/PCINT3)_17") (pintype "bidirectional"))
    )
    (net (code "39") (name "MOSI") (class "Default")
      (node (ref "10H") (pin "4") (pinfunction "4_4") (pintype "bidirectional"))
      (node (ref "ICSP") (pin "4") (pinfunction "4_4") (pintype "bidirectional"))
      (node (ref "ZU4") (pin "15") (pinfunction "PB3_[PCINT3]_15") (pintype "bidirectional"))
    )
    (net (code "40") (name "MOSI2") (class "Default")
      (node (ref "ICSP1") (pin "4") (pinfunction "4_4") (pintype "bidirectional"))
      (node (ref "U3") (pin "16") (pinfunction "PB2_(PDI/MOSI/PCINT2)_16") (pintype "bidirectional"))
    )
    (net (code "41") (name "Net-(D3-K)") (class "Default")
      (node (ref "D3") (pin "1") (pinfunction "K_1") (pintype "bidirectional"))
      (node (ref "U1") (pin "3") (pinfunction "IN_3") (pintype "input"))
    )
    (net (code "42") (name "Net-(L-CATHODE__RED)") (class "Default")
      (node (ref "1K_RN2A") (pin "8") (pinfunction "8_8") (pintype "bidirectional"))
      (node (ref "L") (pin "2") (pinfunction "CATHODE__RED_2") (pintype "bidirectional"))
    )
    (net (code "43") (name "Net-(PC2-+)") (class "Default")
      (node (ref "C9") (pin "1") (pinfunction "1_1") (pintype "bidirectional"))
      (node (ref "PC2") (pin "1") (pinfunction "+_1") (pintype "bidirectional"))
      (node (ref "U1") (pin "2") (pinfunction "OUT_1_2") (pintype "output"))
      (node (ref "U1") (pin "4") (pinfunction "OUT_2_4") (pintype "output"))
    )
    (net (code "44") (name "PB4") (class "Default")
      (node (ref "JP2") (pin "1") (pinfunction "1_1") (pintype "bidirectional"))
      (node (ref "U3") (pin "18") (pinfunction "PB4_(T1/PCINT4)_18") (pintype "bidirectional"))
    )
    (net (code "45") (name "PB5") (class "Default")
      (node (ref "JP2") (pin "3") (pinfunction "3_3") (pintype "bidirectional"))
      (node (ref "U3") (pin "19") (pinfunction "PB5_(PCINT5)_19") (pintype "bidirectional"))
    )
    (net (code "46") (name "PB6") (class "Default")
      (node (ref "JP2") (pin "2") (pinfunction "2_2") (pintype "bidirectional"))
      (node (ref "U3") (pin "20") (pinfunction "PB6_(PCINT6)_20") (pintype "bidirectional"))
    )
    (net (code "47") (name "PB7") (class "Default")
      (node (ref "JP2") (pin "4") (pinfunction "4_4") (pintype "bidirectional"))
      (node (ref "U3") (pin "21") (pinfunction "PB7_(PCINT7/OC.0A/OC.1C)_21") (pintype "bidirectional"))
    )
    (net (code "48") (name "PWRIN") (class "Default")
      (node (ref "D3") (pin "2") (pinfunction "A_2") (pintype "bidirectional"))
      (node (ref "PC1") (pin "1") (pinfunction "+_1") (pintype "bidirectional"))
      (node (ref "X1") (pin "2") (pinfunction "2_2") (pintype "bidirectional"))
    )
    (net (code "49") (name "RD+") (class "Default")
      (node (ref "22R_RN") (pin "7") (pinfunction "7_7") (pintype "bidirectional"))
      (node (ref "U3") (pin "29") (pinfunction "D+_29") (pintype "bidirectional"))
    )
    (net (code "50") (name "RD-") (class "Default")
      (node (ref "22R_RN") (pin "8") (pinfunction "8_8") (pintype "bidirectional"))
      (node (ref "U3") (pin "30") (pinfunction "D-_30") (pintype "bidirectional"))
    )
    (net (code "51") (name "RESET") (class "Default")
      (node (ref "10K_RN") (pin "7") (pinfunction "7_7") (pintype "bidirectional"))
      (node (ref "BEED2") (pin "1") (pinfunction "1_1") (pintype "bidirectional"))
      (node (ref "BEED2") (pin "2") (pinfunction "2_2") (pintype "bidirectional"))
      (node (ref "C1") (pin "2") (pinfunction "2_2") (pintype "bidirectional"))
      (node (ref "D2") (pin "2") (pinfunction "A_2") (pintype "bidirectional"))
      (node (ref "ICSP") (pin "5") (pinfunction "5_5") (pintype "bidirectional"))
      (node (ref "POWER") (pin "3") (pinfunction "3_3") (pintype "bidirectional"))
      (node (ref "RESET") (pin "1") (pinfunction "~{RST}_1") (pintype "bidirectional"))
      (node (ref "ZU4") (pin "29") (pinfunction "PC6_[RESET/PCINT14]_29") (pintype "bidirectional"))
    )
    (net (code "52") (name "RESET2") (class "Default")
      (node (ref "10K_RN") (pin "8") (pinfunction "8_8") (pintype "bidirectional"))
      (node (ref "D_3") (pin "2") (pinfunction "A_2") (pintype "bidirectional"))
      (node (ref "ICSP1") (pin "5") (pinfunction "5_5") (pintype "bidirectional"))
      (node (ref "U3") (pin "24") (pinfunction "~{RESET_(PC1}/DW)_24") (pintype "bidirectional"))
    )
    (net (code "53") (name "RXLED") (class "Default")
      (node (ref "LED1") (pin "3") (pinfunction "ANODE_GREEN_3") (pintype "bidirectional"))
      (node (ref "U3") (pin "10") (pinfunction "PD4_(INT5/AIN3)_10") (pintype "bidirectional"))
    )
    (net (code "54") (name "SCK") (class "Default")
      (node (ref "10H") (pin "6") (pinfunction "6_6") (pintype "bidirectional"))
      (node (ref "ICSP") (pin "3") (pinfunction "3_3") (pintype "bidirectional"))
      (node (ref "U5A") (pin "5") (pinfunction "2IN+_5") (pintype "input"))
      (node (ref "ZU4") (pin "17") (pinfunction "PB5_[PCINT5]_17") (pintype "bidirectional"))
    )
    (net (code "55") (name "SCK2") (class "Default")
      (node (ref "ICSP1") (pin "3") (pinfunction "3_3") (pintype "bidirectional"))
      (node (ref "U3") (pin "15") (pinfunction "PB1_(SCLK/PCINT1)_15") (pintype "bidirectional"))
    )
    (net (code "56") (name "SS") (class "Default")
      (node (ref "10H") (pin "3") (pinfunction "3_3") (pintype "bidirectional"))
      (node (ref "ZU4") (pin "14") (pinfunction "PB2_[PCINT2]_14") (pintype "bidirectional"))
    )
    (net (code "57") (name "TP_VUCAP") (class "Default")
      (node (ref "C5") (pin "2") (pinfunction "2_2") (pintype "bidirectional"))
      (node (ref "U3") (pin "27") (pinfunction "UCAP_27") (pintype "bidirectional"))
    )
    (net (code "58") (name "TXLED") (class "Default")
      (node (ref "LED1") (pin "1") (pinfunction "ANODE_RED_1") (pintype "bidirectional"))
      (node (ref "U3") (pin "11") (pinfunction "PD5_(XCK/AIN4/PCINT12)_11") (pintype "bidirectional"))
    )
    (net (code "59") (name "UGND") (class "Default")
      (node (ref "BEAD1") (pin "1") (pinfunction "1_1") (pintype "bidirectional"))
      (node (ref "C5") (pin "1") (pinfunction "1_1") (pintype "bidirectional"))
      (node (ref "L1") (pin "1") (pinfunction "1_1") (pintype "bidirectional"))
      (node (ref "U3") (pin "28") (pinfunction "UGND_28") (pintype "bidirectional"))
      (node (ref "X2") (pin "4") (pinfunction "4_4") (pintype "bidirectional"))
    )
    (net (code "60") (name "USBVCC") (class "Default")
      (node (ref "F1") (pin "2") (pinfunction "2_2") (pintype "bidirectional"))
      (node (ref "T1") (pin "3") (pinfunction "D_3") (pintype "bidirectional"))
      (node (ref "U3") (pin "31") (pinfunction "UVCC_31") (pintype "bidirectional"))
    )
    (net (code "61") (name "USHIELD") (class "Default")
      (node (ref "L1") (pin "2") (pinfunction "2_2") (pintype "bidirectional"))
      (node (ref "X2") (pin "10") (pinfunction "10_10") (pintype "bidirectional"))
      (node (ref "X2") (pin "11") (pinfunction "11_11") (pintype "bidirectional"))
      (node (ref "X2") (pin "5") (pinfunction "5_5") (pintype "bidirectional"))
      (node (ref "X2") (pin "6") (pinfunction "6_6") (pintype "bidirectional"))
      (node (ref "X2") (pin "7") (pinfunction "7_7") (pintype "bidirectional"))
      (node (ref "X2") (pin "8") (pinfunction "8_8") (pintype "bidirectional"))
      (node (ref "X2") (pin "9") (pinfunction "9_9") (pintype "bidirectional"))
      (node (ref "Z1") (pin "1") (pinfunction "1_1") (pintype "bidirectional"))
      (node (ref "Z2") (pin "1") (pinfunction "1_1") (pintype "bidirectional"))
    )
    (net (code "62") (name "VIN") (class "Default")
      (node (ref "10K_RN2") (pin "1") (pinfunction "1_1") (pintype "bidirectional"))
      (node (ref "POWER") (pin "8") (pinfunction "8_8") (pintype "bidirectional"))
    )
    (net (code "63") (name "XT1") (class "Default")
      (node (ref "C10") (pin "2") (pinfunction "2_2") (pintype "bidirectional"))
      (node (ref "R1") (pin "2") (pinfunction "2_2") (pintype "bidirectional"))
      (node (ref "U3") (pin "1") (pinfunction "XTAL1_1") (pintype "bidirectional"))
      (node (ref "XTI") (pin "2") (pinfunction "2_2") (pintype "bidirectional"))
    )
    (net (code "64") (name "XT2") (class "Default")
      (node (ref "C4") (pin "2") (pinfunction "2_2") (pintype "bidirectional"))
      (node (ref "R1") (pin "1") (pinfunction "1_1") (pintype "bidirectional"))
      (node (ref "U3") (pin "2") (pinfunction "(PC0)_XTAL2_2") (pintype "bidirectional"))
      (node (ref "XTI") (pin "1") (pinfunction "1_1") (pintype "bidirectional"))
    )
    (net (code "65") (name "XT2_1") (class "Default")
      (node (ref "R2") (pin "1") (pinfunction "1_1") (pintype "bidirectional"))
      (node (ref "XT") (pin "1") (pinfunction "1_1") (pintype "bidirectional"))
    )
    (net (code "66") (name "XT2_2") (class "Default")
      (node (ref "R2") (pin "2") (pinfunction "2_2") (pintype "bidirectional"))
      (node (ref "XT") (pin "2") (pinfunction "2_2") (pintype "bidirectional"))
    )
    (net (code "67") (name "XT_1") (class "Default")
      (node (ref "ZU4") (pin "7") (pinfunction "PB6_[PCINT6]_7") (pintype "bidirectional"))
    )
    (net (code "68") (name "XT_2") (class "Default")
      (node (ref "ZU4") (pin "8") (pinfunction "PB7_[PCINT7]_8") (pintype "bidirectional"))
    )
    (net (code "69") (name "XUSB") (class "Default")
      (node (ref "F1") (pin "1") (pinfunction "1_1") (pintype "bidirectional"))
      (node (ref "X2") (pin "1") (pinfunction "1_1") (pintype "bidirectional"))
    )
    (net (code "70") (name "unconnected-(1K_RN-Pad2)") (class "Default")
      (node (ref "1K_RN") (pin "2") (pinfunction "2_2") (pintype "bidirectional"))
    )
    (net (code "71") (name "unconnected-(1K_RN-Pad3)") (class "Default")
      (node (ref "1K_RN") (pin "3") (pinfunction "3_3") (pintype "bidirectional"))
    )
    (net (code "72") (name "unconnected-(1K_RN-Pad4)") (class "Default")
      (node (ref "1K_RN") (pin "4") (pinfunction "4_4") (pintype "bidirectional"))
    )
    (net (code "73") (name "unconnected-(1K_RN-Pad5)") (class "Default")
      (node (ref "1K_RN") (pin "5") (pinfunction "5_5") (pintype "bidirectional"))
    )
    (net (code "74") (name "unconnected-(1K_RN-Pad6)") (class "Default")
      (node (ref "1K_RN") (pin "6") (pinfunction "6_6") (pintype "bidirectional"))
    )
    (net (code "75") (name "unconnected-(1K_RN-Pad7)") (class "Default")
      (node (ref "1K_RN") (pin "7") (pinfunction "7_7") (pintype "bidirectional"))
    )
    (net (code "76") (name "unconnected-(1K_RN2A-Pad4)") (class "Default")
      (node (ref "1K_RN2A") (pin "4") (pinfunction "4_4") (pintype "bidirectional"))
    )
    (net (code "77") (name "unconnected-(1K_RN2A-Pad5)") (class "Default")
      (node (ref "1K_RN2A") (pin "5") (pinfunction "5_5") (pintype "bidirectional"))
    )
    (net (code "78") (name "unconnected-(10K_RN-Pad3)") (class "Default")
      (node (ref "10K_RN") (pin "3") (pinfunction "3_3") (pintype "bidirectional"))
    )
    (net (code "79") (name "unconnected-(10K_RN-Pad4)") (class "Default")
      (node (ref "10K_RN") (pin "4") (pinfunction "4_4") (pintype "bidirectional"))
    )
    (net (code "80") (name "unconnected-(10K_RN-Pad5)") (class "Default")
      (node (ref "10K_RN") (pin "5") (pinfunction "5_5") (pintype "bidirectional"))
    )
    (net (code "81") (name "unconnected-(10K_RN-Pad6)") (class "Default")
      (node (ref "10K_RN") (pin "6") (pinfunction "6_6") (pintype "bidirectional"))
    )
    (net (code "82") (name "unconnected-(10K_RN2-Pad3)") (class "Default")
      (node (ref "10K_RN2") (pin "3") (pinfunction "3_3") (pintype "bidirectional"))
    )
    (net (code "83") (name "unconnected-(10K_RN2-Pad4)") (class "Default")
      (node (ref "10K_RN2") (pin "4") (pinfunction "4_4") (pintype "bidirectional"))
    )
    (net (code "84") (name "unconnected-(10K_RN2-Pad5)") (class "Default")
      (node (ref "10K_RN2") (pin "5") (pinfunction "5_5") (pintype "bidirectional"))
    )
    (net (code "85") (name "unconnected-(10K_RN2-Pad6)") (class "Default")
      (node (ref "10K_RN2") (pin "6") (pinfunction "6_6") (pintype "bidirectional"))
    )
    (net (code "86") (name "unconnected-(22R_RN-Pad3)") (class "Default")
      (node (ref "22R_RN") (pin "3") (pinfunction "3_3") (pintype "bidirectional"))
    )
    (net (code "87") (name "unconnected-(22R_RN-Pad4)") (class "Default")
      (node (ref "22R_RN") (pin "4") (pinfunction "4_4") (pintype "bidirectional"))
    )
    (net (code "88") (name "unconnected-(22R_RN-Pad5)") (class "Default")
      (node (ref "22R_RN") (pin "5") (pinfunction "5_5") (pintype "bidirectional"))
    )
    (net (code "89") (name "unconnected-(22R_RN-Pad6)") (class "Default")
      (node (ref "22R_RN") (pin "6") (pinfunction "6_6") (pintype "bidirectional"))
    )
    (net (code "90") (name "unconnected-(AD-Pad7)") (class "Default")
      (node (ref "AD") (pin "7") (pinfunction "7_7") (pintype "bidirectional"))
    )
    (net (code "91") (name "unconnected-(AD-Pad8)") (class "Default")
      (node (ref "AD") (pin "8") (pinfunction "8_8") (pintype "bidirectional"))
    )
    (net (code "92") (name "unconnected-(ICSP-Pad7)") (class "Default")
      (node (ref "ICSP") (pin "7") (pinfunction "7_7") (pintype "bidirectional"))
    )
    (net (code "93") (name "unconnected-(ICSP-Pad8)") (class "Default")
      (node (ref "ICSP") (pin "8") (pinfunction "8_8") (pintype "bidirectional"))
    )
    (net (code "94") (name "unconnected-(ICSP1-Pad7)") (class "Default")
      (node (ref "ICSP1") (pin "7") (pinfunction "7_7") (pintype "bidirectional"))
    )
    (net (code "95") (name "unconnected-(ICSP1-Pad8)") (class "Default")
      (node (ref "ICSP1") (pin "8") (pinfunction "8_8") (pintype "bidirectional"))
    )
    (net (code "96") (name "unconnected-(POWER-Pad1)") (class "Default")
      (node (ref "POWER") (pin "1") (pinfunction "1_1") (pintype "bidirectional"))
    )
    (net (code "97") (name "unconnected-(U2-BYPASS-Pad4)") (class "Default")
      (node (ref "U2") (pin "4") (pinfunction "BYPASS_4") (pintype "bidirectional"))
    )
    (net (code "98") (name "unconnected-(U3-PB0_(~{SS}{slash}PCINT0)-Pad14)") (class "Default")
      (node (ref "U3") (pin "14") (pinfunction "PB0_(~{SS}/PCINT0)_14") (pintype "bidirectional"))
    )
    (net (code "99") (name "unconnected-(U3-PC2_(PCINT11{slash}AIN2)-Pad5)") (class "Default")
      (node (ref "U3") (pin "5") (pinfunction "PC2_(PCINT11/AIN2)_5") (pintype "bidirectional"))
    )
    (net (code "100") (name "unconnected-(U3-PC4_(PCINT10)-Pad26)") (class "Default")
      (node (ref "U3") (pin "26") (pinfunction "PC4_(PCINT10)_26") (pintype "bidirectional"))
    )
    (net (code "101") (name "unconnected-(U3-PC5_(PCINT9{slash}OC.1B)-Pad25)") (class "Default")
      (node (ref "U3") (pin "25") (pinfunction "PC5_(PCINT9/OC.1B)_25") (pintype "bidirectional"))
    )
    (net (code "102") (name "unconnected-(U3-PC6_(OC.1A{slash}PCINT8)-Pad23)") (class "Default")
      (node (ref "U3") (pin "23") (pinfunction "PC6_(OC.1A/PCINT8)_23") (pintype "bidirectional"))
    )
    (net (code "103") (name "unconnected-(U3-PC7_(INT4{slash}ICP1{slash}CLKO)-Pad22)") (class "Default")
      (node (ref "U3") (pin "22") (pinfunction "PC7_(INT4/ICP1/CLKO)_22") (pintype "bidirectional"))
    )
    (net (code "104") (name "unconnected-(U3-PD0_(OC.0B{slash}INT0)-Pad6)") (class "Default")
      (node (ref "U3") (pin "6") (pinfunction "PD0_(OC.0B/INT0)_6") (pintype "bidirectional"))
    )
    (net (code "105") (name "unconnected-(U3-PD1_(AIN0{slash}INT1)-Pad7)") (class "Default")
      (node (ref "U3") (pin "7") (pinfunction "PD1_(AIN0/INT1)_7") (pintype "bidirectional"))
    )
    (net (code "106") (name "unconnected-(U3-PD6_(~{RTS}{slash}AIN5{slash}INT6)-Pad12)") (class "Default")
      (node (ref "U3") (pin "12") (pinfunction "PD6_(~{RTS}/AIN5/INT6)_12") (pintype "bidirectional"))
    )
    (net (code "107") (name "unconnected-(ZU4-ADC6-Pad19)") (class "Default")
      (node (ref "ZU4") (pin "19") (pinfunction "ADC6_19") (pintype "bidirectional"))
    )
    (net (code "108") (name "unconnected-(ZU4-ADC7-Pad22)") (class "Default")
      (node (ref "ZU4") (pin "22") (pinfunction "ADC7_22") (pintype "bidirectional"))
    )
  )
)
